# Resistor_Phantom.net
KiCad netlist of a schematic drawn in EAGLE
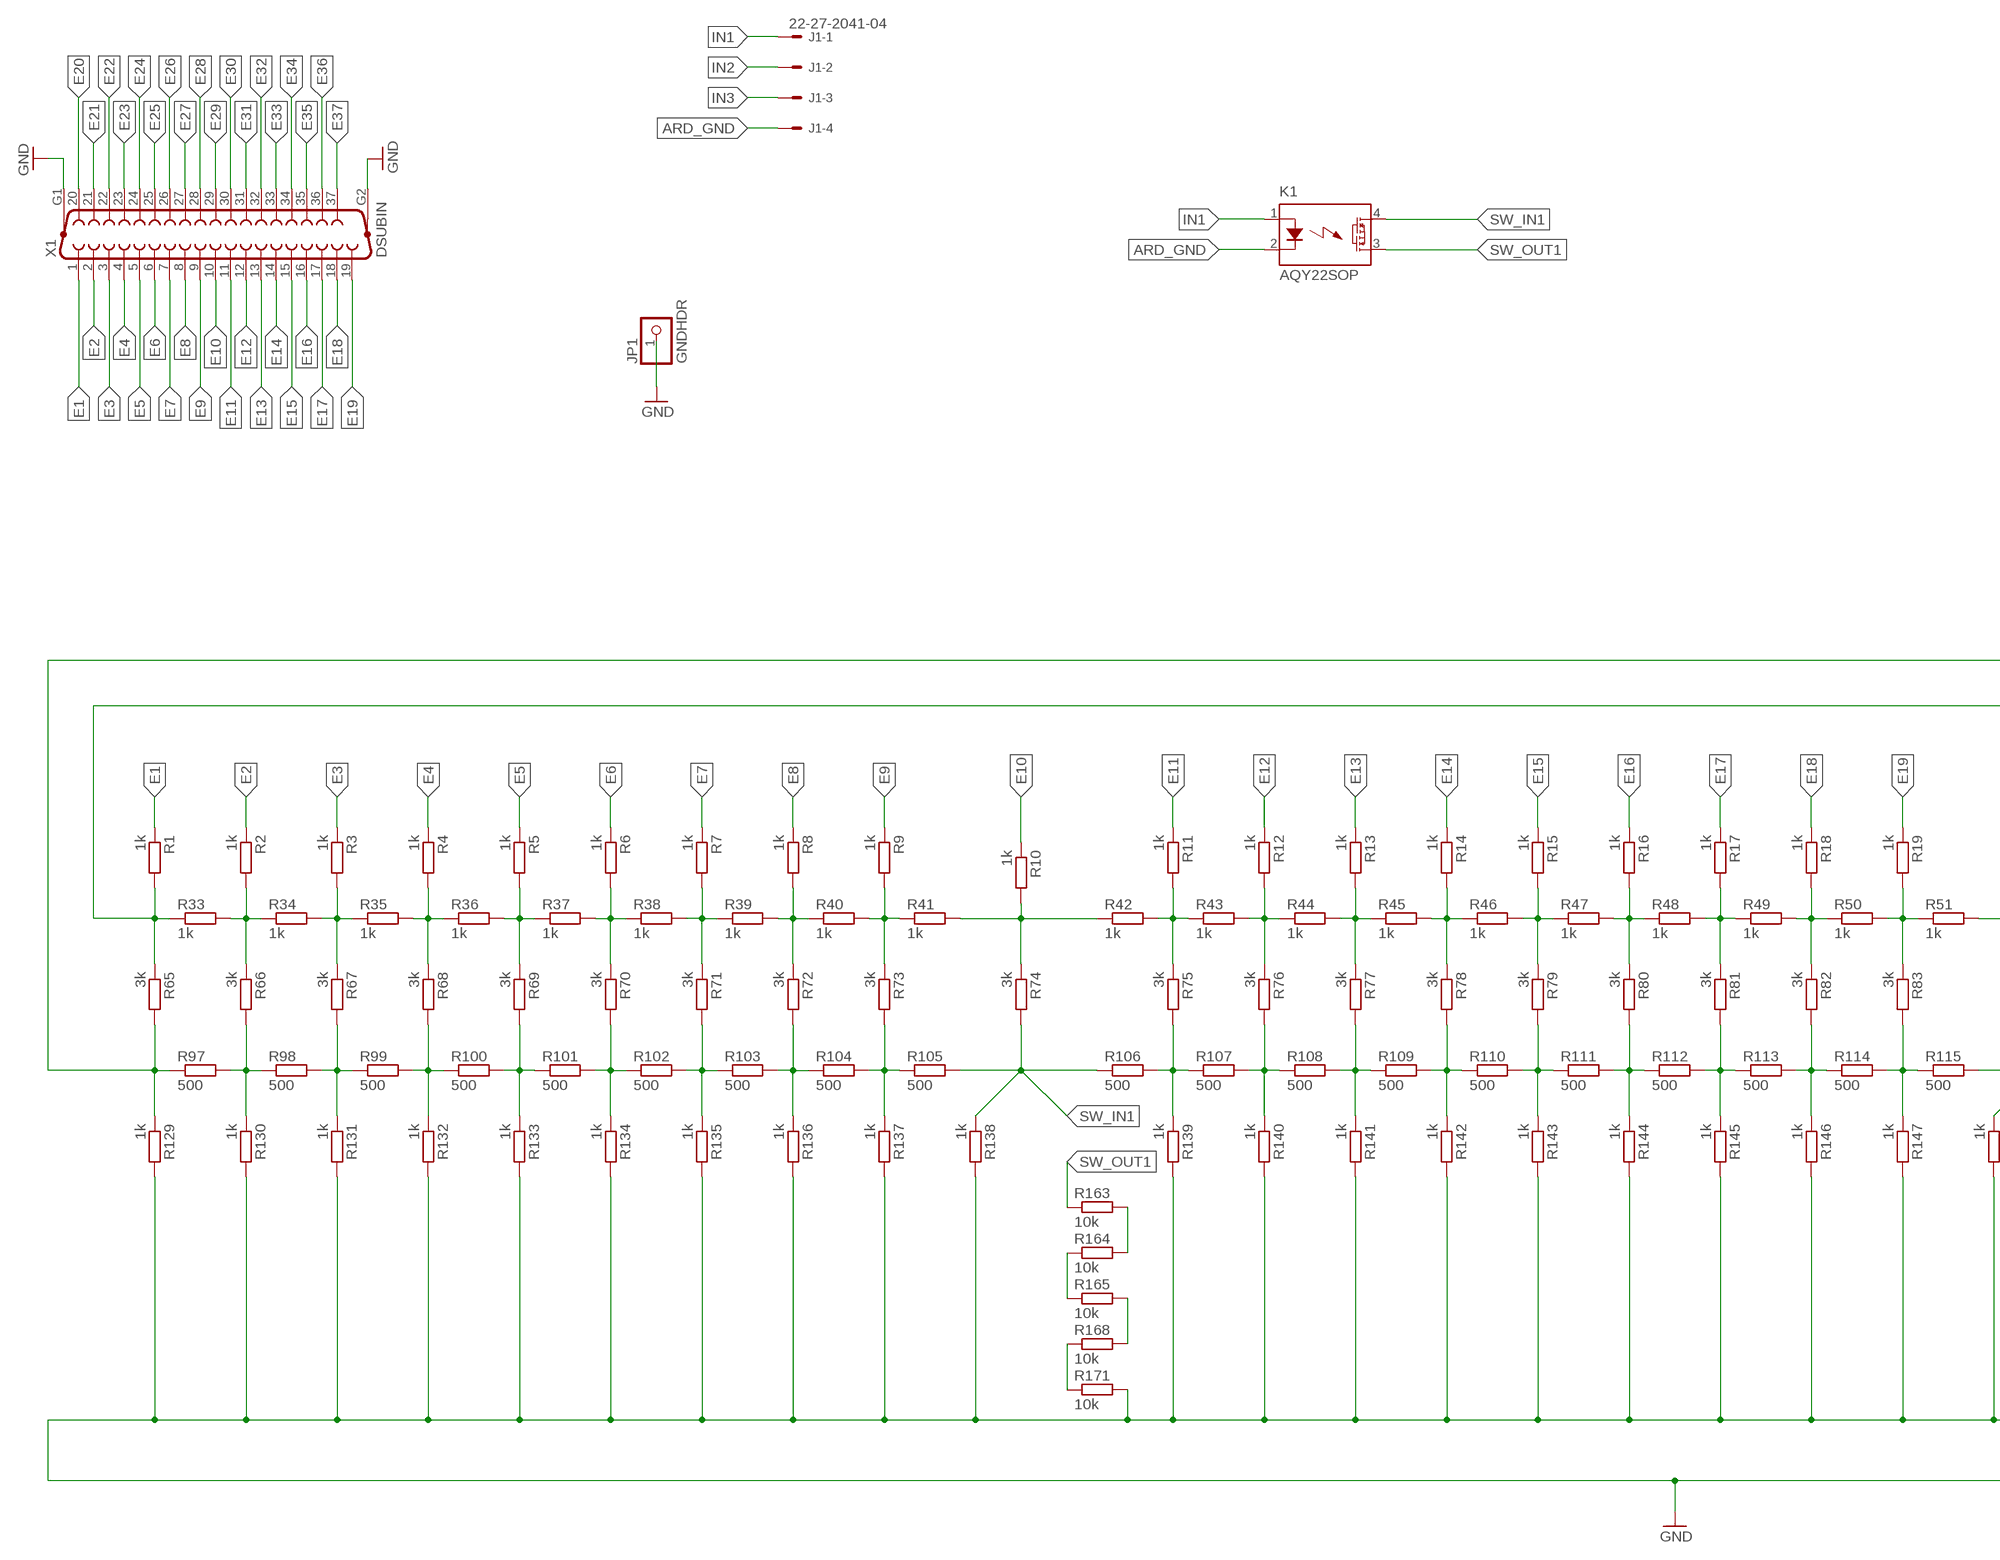
[diagram p0: schematic, sheet 1, part 1 of 2]
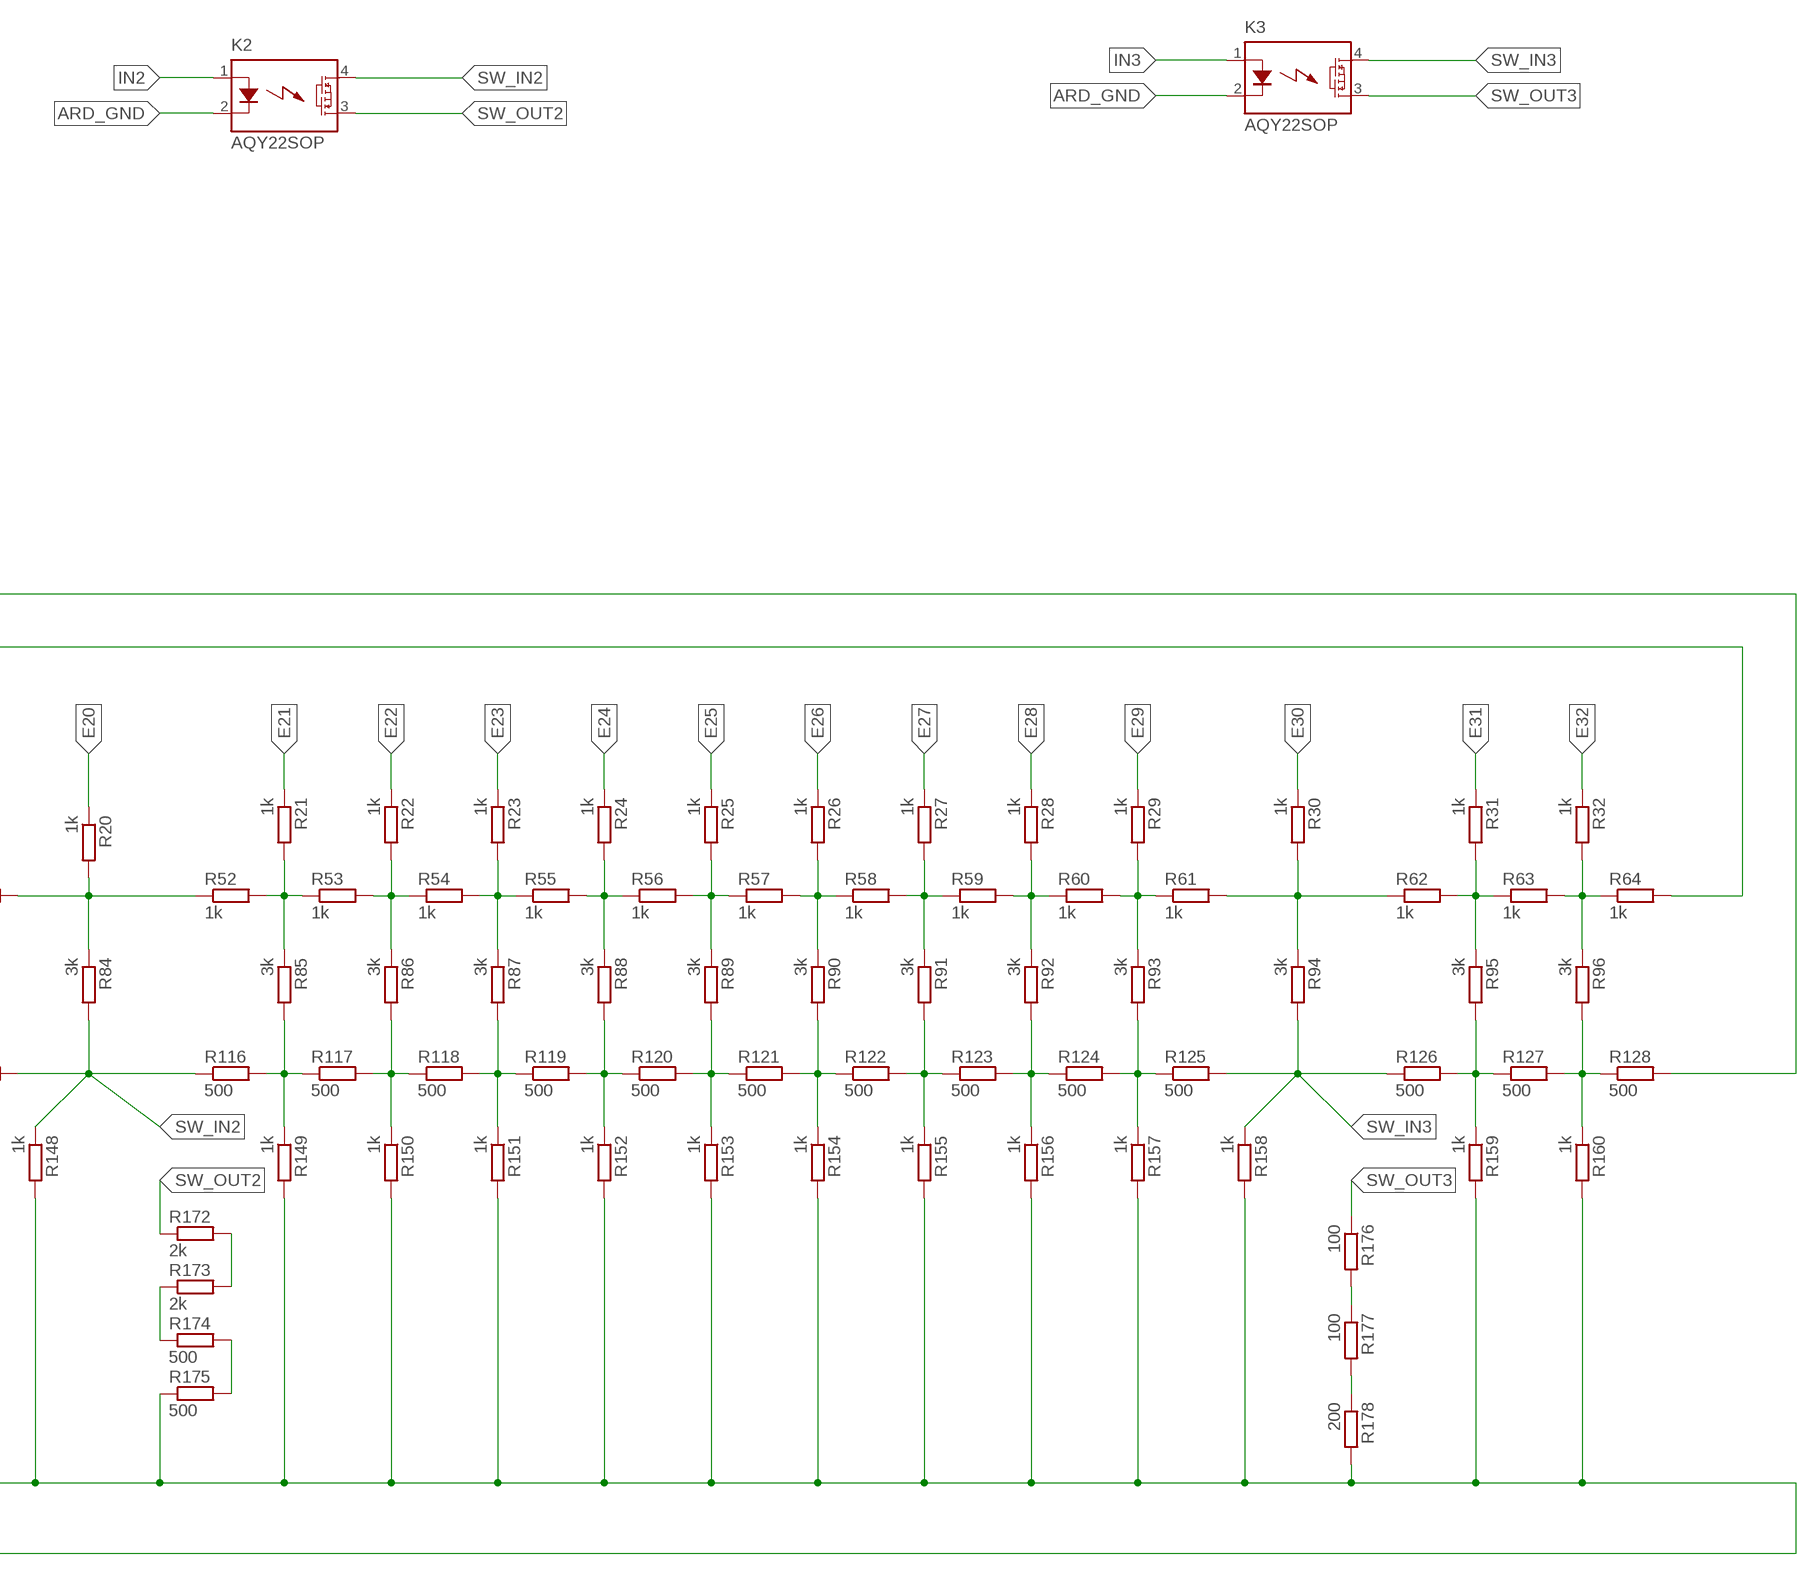
[diagram p1: schematic, sheet 1, part 2 of 2]

(export (version "E")
  (design (tool "Eeschema 10.0.6"))
  (components
    (comp (ref "J1")
      (value "22-27-2041-04")
      (footprint "eagle-import:6410-04")
      (libsource (lib "eagle-import") (part "22-?-0427-2041"))
    )
    (comp (ref "JP1")
      (value "GNDHDR")
      (footprint "eagle-import:1X01")
      (libsource (lib "eagle-import") (part "PINHD-1X1"))
    )
    (comp (ref "K1")
      (value "AQY22SOP")
      (footprint "eagle-import:SOP04")
      (libsource (lib "eagle-import") (part "AQYSOP22"))
    )
    (comp (ref "K2")
      (value "AQY22SOP")
      (footprint "eagle-import:SOP04")
      (libsource (lib "eagle-import") (part "AQYSOP22"))
    )
    (comp (ref "K3")
      (value "AQY22SOP")
      (footprint "eagle-import:SOP04")
      (libsource (lib "eagle-import") (part "AQYSOP22"))
    )
    (comp (ref "R1")
      (value "1k")
      (footprint "eagle-import:R0402")
      (libsource (lib "eagle-import") (part "R-EU_R0402"))
    )
    (comp (ref "R2")
      (value "1k")
      (footprint "eagle-import:R0402")
      (libsource (lib "eagle-import") (part "R-EU_R0402"))
    )
    (comp (ref "R3")
      (value "1k")
      (footprint "eagle-import:R0402")
      (libsource (lib "eagle-import") (part "R-EU_R0402"))
    )
    (comp (ref "R4")
      (value "1k")
      (footprint "eagle-import:R0402")
      (libsource (lib "eagle-import") (part "R-EU_R0402"))
    )
    (comp (ref "R5")
      (value "1k")
      (footprint "eagle-import:R0402")
      (libsource (lib "eagle-import") (part "R-EU_R0402"))
    )
    (comp (ref "R6")
      (value "1k")
      (footprint "eagle-import:R0402")
      (libsource (lib "eagle-import") (part "R-EU_R0402"))
    )
    (comp (ref "R7")
      (value "1k")
      (footprint "eagle-import:R0402")
      (libsource (lib "eagle-import") (part "R-EU_R0402"))
    )
    (comp (ref "R8")
      (value "1k")
      (footprint "eagle-import:R0402")
      (libsource (lib "eagle-import") (part "R-EU_R0402"))
    )
    (comp (ref "R9")
      (value "1k")
      (footprint "eagle-import:R0402")
      (libsource (lib "eagle-import") (part "R-EU_R0402"))
    )
    (comp (ref "R10")
      (value "1k")
      (footprint "eagle-import:R0402")
      (libsource (lib "eagle-import") (part "R-EU_R0402"))
    )
    (comp (ref "R11")
      (value "1k")
      (footprint "eagle-import:R0402")
      (libsource (lib "eagle-import") (part "R-EU_R0402"))
    )
    (comp (ref "R12")
      (value "1k")
      (footprint "eagle-import:R0402")
      (libsource (lib "eagle-import") (part "R-EU_R0402"))
    )
    (comp (ref "R13")
      (value "1k")
      (footprint "eagle-import:R0402")
      (libsource (lib "eagle-import") (part "R-EU_R0402"))
    )
    (comp (ref "R14")
      (value "1k")
      (footprint "eagle-import:R0402")
      (libsource (lib "eagle-import") (part "R-EU_R0402"))
    )
    (comp (ref "R15")
      (value "1k")
      (footprint "eagle-import:R0402")
      (libsource (lib "eagle-import") (part "R-EU_R0402"))
    )
    (comp (ref "R16")
      (value "1k")
      (footprint "eagle-import:R0402")
      (libsource (lib "eagle-import") (part "R-EU_R0402"))
    )
    (comp (ref "R17")
      (value "1k")
      (footprint "eagle-import:R0402")
      (libsource (lib "eagle-import") (part "R-EU_R0402"))
    )
    (comp (ref "R18")
      (value "1k")
      (footprint "eagle-import:R0402")
      (libsource (lib "eagle-import") (part "R-EU_R0402"))
    )
    (comp (ref "R19")
      (value "1k")
      (footprint "eagle-import:R0402")
      (libsource (lib "eagle-import") (part "R-EU_R0402"))
    )
    (comp (ref "R20")
      (value "1k")
      (footprint "eagle-import:R0402")
      (libsource (lib "eagle-import") (part "R-EU_R0402"))
    )
    (comp (ref "R21")
      (value "1k")
      (footprint "eagle-import:R0402")
      (libsource (lib "eagle-import") (part "R-EU_R0402"))
    )
    (comp (ref "R22")
      (value "1k")
      (footprint "eagle-import:R0402")
      (libsource (lib "eagle-import") (part "R-EU_R0402"))
    )
    (comp (ref "R23")
      (value "1k")
      (footprint "eagle-import:R0402")
      (libsource (lib "eagle-import") (part "R-EU_R0402"))
    )
    (comp (ref "R24")
      (value "1k")
      (footprint "eagle-import:R0402")
      (libsource (lib "eagle-import") (part "R-EU_R0402"))
    )
    (comp (ref "R25")
      (value "1k")
      (footprint "eagle-import:R0402")
      (libsource (lib "eagle-import") (part "R-EU_R0402"))
    )
    (comp (ref "R26")
      (value "1k")
      (footprint "eagle-import:R0402")
      (libsource (lib "eagle-import") (part "R-EU_R0402"))
    )
    (comp (ref "R27")
      (value "1k")
      (footprint "eagle-import:R0402")
      (libsource (lib "eagle-import") (part "R-EU_R0402"))
    )
    (comp (ref "R28")
      (value "1k")
      (footprint "eagle-import:R0402")
      (libsource (lib "eagle-import") (part "R-EU_R0402"))
    )
    (comp (ref "R29")
      (value "1k")
      (footprint "eagle-import:R0402")
      (libsource (lib "eagle-import") (part "R-EU_R0402"))
    )
    (comp (ref "R30")
      (value "1k")
      (footprint "eagle-import:R0402")
      (libsource (lib "eagle-import") (part "R-EU_R0402"))
    )
    (comp (ref "R31")
      (value "1k")
      (footprint "eagle-import:R0402")
      (libsource (lib "eagle-import") (part "R-EU_R0402"))
    )
    (comp (ref "R32")
      (value "1k")
      (footprint "eagle-import:R0402")
      (libsource (lib "eagle-import") (part "R-EU_R0402"))
    )
    (comp (ref "R33")
      (value "1k")
      (footprint "eagle-import:R0402")
      (libsource (lib "eagle-import") (part "R-EU_R0402"))
    )
    (comp (ref "R34")
      (value "1k")
      (footprint "eagle-import:R0402")
      (libsource (lib "eagle-import") (part "R-EU_R0402"))
    )
    (comp (ref "R35")
      (value "1k")
      (footprint "eagle-import:R0402")
      (libsource (lib "eagle-import") (part "R-EU_R0402"))
    )
    (comp (ref "R36")
      (value "1k")
      (footprint "eagle-import:R0402")
      (libsource (lib "eagle-import") (part "R-EU_R0402"))
    )
    (comp (ref "R37")
      (value "1k")
      (footprint "eagle-import:R0402")
      (libsource (lib "eagle-import") (part "R-EU_R0402"))
    )
    (comp (ref "R38")
      (value "1k")
      (footprint "eagle-import:R0402")
      (libsource (lib "eagle-import") (part "R-EU_R0402"))
    )
    (comp (ref "R39")
      (value "1k")
      (footprint "eagle-import:R0402")
      (libsource (lib "eagle-import") (part "R-EU_R0402"))
    )
    (comp (ref "R40")
      (value "1k")
      (footprint "eagle-import:R0402")
      (libsource (lib "eagle-import") (part "R-EU_R0402"))
    )
    (comp (ref "R41")
      (value "1k")
      (footprint "eagle-import:R0402")
      (libsource (lib "eagle-import") (part "R-EU_R0402"))
    )
    (comp (ref "R42")
      (value "1k")
      (footprint "eagle-import:R0402")
      (libsource (lib "eagle-import") (part "R-EU_R0402"))
    )
    (comp (ref "R43")
      (value "1k")
      (footprint "eagle-import:R0402")
      (libsource (lib "eagle-import") (part "R-EU_R0402"))
    )
    (comp (ref "R44")
      (value "1k")
      (footprint "eagle-import:R0402")
      (libsource (lib "eagle-import") (part "R-EU_R0402"))
    )
    (comp (ref "R45")
      (value "1k")
      (footprint "eagle-import:R0402")
      (libsource (lib "eagle-import") (part "R-EU_R0402"))
    )
    (comp (ref "R46")
      (value "1k")
      (footprint "eagle-import:R0402")
      (libsource (lib "eagle-import") (part "R-EU_R0402"))
    )
    (comp (ref "R47")
      (value "1k")
      (footprint "eagle-import:R0402")
      (libsource (lib "eagle-import") (part "R-EU_R0402"))
    )
    (comp (ref "R48")
      (value "1k")
      (footprint "eagle-import:R0402")
      (libsource (lib "eagle-import") (part "R-EU_R0402"))
    )
    (comp (ref "R49")
      (value "1k")
      (footprint "eagle-import:R0402")
      (libsource (lib "eagle-import") (part "R-EU_R0402"))
    )
    (comp (ref "R50")
      (value "1k")
      (footprint "eagle-import:R0402")
      (libsource (lib "eagle-import") (part "R-EU_R0402"))
    )
    (comp (ref "R51")
      (value "1k")
      (footprint "eagle-import:R0402")
      (libsource (lib "eagle-import") (part "R-EU_R0402"))
    )
    (comp (ref "R52")
      (value "1k")
      (footprint "eagle-import:R0402")
      (libsource (lib "eagle-import") (part "R-EU_R0402"))
    )
    (comp (ref "R53")
      (value "1k")
      (footprint "eagle-import:R0402")
      (libsource (lib "eagle-import") (part "R-EU_R0402"))
    )
    (comp (ref "R54")
      (value "1k")
      (footprint "eagle-import:R0402")
      (libsource (lib "eagle-import") (part "R-EU_R0402"))
    )
    (comp (ref "R55")
      (value "1k")
      (footprint "eagle-import:R0402")
      (libsource (lib "eagle-import") (part "R-EU_R0402"))
    )
    (comp (ref "R56")
      (value "1k")
      (footprint "eagle-import:R0402")
      (libsource (lib "eagle-import") (part "R-EU_R0402"))
    )
    (comp (ref "R57")
      (value "1k")
      (footprint "eagle-import:R0402")
      (libsource (lib "eagle-import") (part "R-EU_R0402"))
    )
    (comp (ref "R58")
      (value "1k")
      (footprint "eagle-import:R0402")
      (libsource (lib "eagle-import") (part "R-EU_R0402"))
    )
    (comp (ref "R59")
      (value "1k")
      (footprint "eagle-import:R0402")
      (libsource (lib "eagle-import") (part "R-EU_R0402"))
    )
    (comp (ref "R60")
      (value "1k")
      (footprint "eagle-import:R0402")
      (libsource (lib "eagle-import") (part "R-EU_R0402"))
    )
    (comp (ref "R61")
      (value "1k")
      (footprint "eagle-import:R0402")
      (libsource (lib "eagle-import") (part "R-EU_R0402"))
    )
    (comp (ref "R62")
      (value "1k")
      (footprint "eagle-import:R0402")
      (libsource (lib "eagle-import") (part "R-EU_R0402"))
    )
    (comp (ref "R63")
      (value "1k")
      (footprint "eagle-import:R0402")
      (libsource (lib "eagle-import") (part "R-EU_R0402"))
    )
    (comp (ref "R64")
      (value "1k")
      (footprint "eagle-import:R0402")
      (libsource (lib "eagle-import") (part "R-EU_R0402"))
    )
    (comp (ref "R65")
      (value "3k")
      (footprint "eagle-import:R0402")
      (libsource (lib "eagle-import") (part "R-EU_R0402"))
    )
    (comp (ref "R66")
      (value "3k")
      (footprint "eagle-import:R0402")
      (libsource (lib "eagle-import") (part "R-EU_R0402"))
    )
    (comp (ref "R67")
      (value "3k")
      (footprint "eagle-import:R0402")
      (libsource (lib "eagle-import") (part "R-EU_R0402"))
    )
    (comp (ref "R68")
      (value "3k")
      (footprint "eagle-import:R0402")
      (libsource (lib "eagle-import") (part "R-EU_R0402"))
    )
    (comp (ref "R69")
      (value "3k")
      (footprint "eagle-import:R0402")
      (libsource (lib "eagle-import") (part "R-EU_R0402"))
    )
    (comp (ref "R70")
      (value "3k")
      (footprint "eagle-import:R0402")
      (libsource (lib "eagle-import") (part "R-EU_R0402"))
    )
    (comp (ref "R71")
      (value "3k")
      (footprint "eagle-import:R0402")
      (libsource (lib "eagle-import") (part "R-EU_R0402"))
    )
    (comp (ref "R72")
      (value "3k")
      (footprint "eagle-import:R0402")
      (libsource (lib "eagle-import") (part "R-EU_R0402"))
    )
    (comp (ref "R73")
      (value "3k")
      (footprint "eagle-import:R0402")
      (libsource (lib "eagle-import") (part "R-EU_R0402"))
    )
    (comp (ref "R74")
      (value "3k")
      (footprint "eagle-import:R0402")
      (libsource (lib "eagle-import") (part "R-EU_R0402"))
    )
    (comp (ref "R75")
      (value "3k")
      (footprint "eagle-import:R0402")
      (libsource (lib "eagle-import") (part "R-EU_R0402"))
    )
    (comp (ref "R76")
      (value "3k")
      (footprint "eagle-import:R0402")
      (libsource (lib "eagle-import") (part "R-EU_R0402"))
    )
    (comp (ref "R77")
      (value "3k")
      (footprint "eagle-import:R0402")
      (libsource (lib "eagle-import") (part "R-EU_R0402"))
    )
    (comp (ref "R78")
      (value "3k")
      (footprint "eagle-import:R0402")
      (libsource (lib "eagle-import") (part "R-EU_R0402"))
    )
    (comp (ref "R79")
      (value "3k")
      (footprint "eagle-import:R0402")
      (libsource (lib "eagle-import") (part "R-EU_R0402"))
    )
    (comp (ref "R80")
      (value "3k")
      (footprint "eagle-import:R0402")
      (libsource (lib "eagle-import") (part "R-EU_R0402"))
    )
    (comp (ref "R81")
      (value "3k")
      (footprint "eagle-import:R0402")
      (libsource (lib "eagle-import") (part "R-EU_R0402"))
    )
    (comp (ref "R82")
      (value "3k")
      (footprint "eagle-import:R0402")
      (libsource (lib "eagle-import") (part "R-EU_R0402"))
    )
    (comp (ref "R83")
      (value "3k")
      (footprint "eagle-import:R0402")
      (libsource (lib "eagle-import") (part "R-EU_R0402"))
    )
    (comp (ref "R84")
      (value "3k")
      (footprint "eagle-import:R0402")
      (libsource (lib "eagle-import") (part "R-EU_R0402"))
    )
    (comp (ref "R85")
      (value "3k")
      (footprint "eagle-import:R0402")
      (libsource (lib "eagle-import") (part "R-EU_R0402"))
    )
    (comp (ref "R86")
      (value "3k")
      (footprint "eagle-import:R0402")
      (libsource (lib "eagle-import") (part "R-EU_R0402"))
    )
    (comp (ref "R87")
      (value "3k")
      (footprint "eagle-import:R0402")
      (libsource (lib "eagle-import") (part "R-EU_R0402"))
    )
    (comp (ref "R88")
      (value "3k")
      (footprint "eagle-import:R0402")
      (libsource (lib "eagle-import") (part "R-EU_R0402"))
    )
    (comp (ref "R89")
      (value "3k")
      (footprint "eagle-import:R0402")
      (libsource (lib "eagle-import") (part "R-EU_R0402"))
    )
    (comp (ref "R90")
      (value "3k")
      (footprint "eagle-import:R0402")
      (libsource (lib "eagle-import") (part "R-EU_R0402"))
    )
    (comp (ref "R91")
      (value "3k")
      (footprint "eagle-import:R0402")
      (libsource (lib "eagle-import") (part "R-EU_R0402"))
    )
    (comp (ref "R92")
      (value "3k")
      (footprint "eagle-import:R0402")
      (libsource (lib "eagle-import") (part "R-EU_R0402"))
    )
    (comp (ref "R93")
      (value "3k")
      (footprint "eagle-import:R0402")
      (libsource (lib "eagle-import") (part "R-EU_R0402"))
    )
    (comp (ref "R94")
      (value "3k")
      (footprint "eagle-import:R0402")
      (libsource (lib "eagle-import") (part "R-EU_R0402"))
    )
    (comp (ref "R95")
      (value "3k")
      (footprint "eagle-import:R0402")
      (libsource (lib "eagle-import") (part "R-EU_R0402"))
    )
    (comp (ref "R96")
      (value "3k")
      (footprint "eagle-import:R0402")
      (libsource (lib "eagle-import") (part "R-EU_R0402"))
    )
    (comp (ref "R97")
      (value "500")
      (footprint "eagle-import:R0402")
      (libsource (lib "eagle-import") (part "R-EU_R0402"))
    )
    (comp (ref "R98")
      (value "500")
      (footprint "eagle-import:R0402")
      (libsource (lib "eagle-import") (part "R-EU_R0402"))
    )
    (comp (ref "R99")
      (value "500")
      (footprint "eagle-import:R0402")
      (libsource (lib "eagle-import") (part "R-EU_R0402"))
    )
    (comp (ref "R100")
      (value "500")
      (footprint "eagle-import:R0402")
      (libsource (lib "eagle-import") (part "R-EU_R0402"))
    )
    (comp (ref "R101")
      (value "500")
      (footprint "eagle-import:R0402")
      (libsource (lib "eagle-import") (part "R-EU_R0402"))
    )
    (comp (ref "R102")
      (value "500")
      (footprint "eagle-import:R0402")
      (libsource (lib "eagle-import") (part "R-EU_R0402"))
    )
    (comp (ref "R103")
      (value "500")
      (footprint "eagle-import:R0402")
      (libsource (lib "eagle-import") (part "R-EU_R0402"))
    )
    (comp (ref "R104")
      (value "500")
      (footprint "eagle-import:R0402")
      (libsource (lib "eagle-import") (part "R-EU_R0402"))
    )
    (comp (ref "R105")
      (value "500")
      (footprint "eagle-import:R0402")
      (libsource (lib "eagle-import") (part "R-EU_R0402"))
    )
    (comp (ref "R106")
      (value "500")
      (footprint "eagle-import:R0402")
      (libsource (lib "eagle-import") (part "R-EU_R0402"))
    )
    (comp (ref "R107")
      (value "500")
      (footprint "eagle-import:R0402")
      (libsource (lib "eagle-import") (part "R-EU_R0402"))
    )
    (comp (ref "R108")
      (value "500")
      (footprint "eagle-import:R0402")
      (libsource (lib "eagle-import") (part "R-EU_R0402"))
    )
    (comp (ref "R109")
      (value "500")
      (footprint "eagle-import:R0402")
      (libsource (lib "eagle-import") (part "R-EU_R0402"))
    )
    (comp (ref "R110")
      (value "500")
      (footprint "eagle-import:R0402")
      (libsource (lib "eagle-import") (part "R-EU_R0402"))
    )
    (comp (ref "R111")
      (value "500")
      (footprint "eagle-import:R0402")
      (libsource (lib "eagle-import") (part "R-EU_R0402"))
    )
    (comp (ref "R112")
      (value "500")
      (footprint "eagle-import:R0402")
      (libsource (lib "eagle-import") (part "R-EU_R0402"))
    )
    (comp (ref "R113")
      (value "500")
      (footprint "eagle-import:R0402")
      (libsource (lib "eagle-import") (part "R-EU_R0402"))
    )
    (comp (ref "R114")
      (value "500")
      (footprint "eagle-import:R0402")
      (libsource (lib "eagle-import") (part "R-EU_R0402"))
    )
    (comp (ref "R115")
      (value "500")
      (footprint "eagle-import:R0402")
      (libsource (lib "eagle-import") (part "R-EU_R0402"))
    )
    (comp (ref "R116")
      (value "500")
      (footprint "eagle-import:R0402")
      (libsource (lib "eagle-import") (part "R-EU_R0402"))
    )
    (comp (ref "R117")
      (value "500")
      (footprint "eagle-import:R0402")
      (libsource (lib "eagle-import") (part "R-EU_R0402"))
    )
    (comp (ref "R118")
      (value "500")
      (footprint "eagle-import:R0402")
      (libsource (lib "eagle-import") (part "R-EU_R0402"))
    )
    (comp (ref "R119")
      (value "500")
      (footprint "eagle-import:R0402")
      (libsource (lib "eagle-import") (part "R-EU_R0402"))
    )
    (comp (ref "R120")
      (value "500")
      (footprint "eagle-import:R0402")
      (libsource (lib "eagle-import") (part "R-EU_R0402"))
    )
    (comp (ref "R121")
      (value "500")
      (footprint "eagle-import:R0402")
      (libsource (lib "eagle-import") (part "R-EU_R0402"))
    )
    (comp (ref "R122")
      (value "500")
      (footprint "eagle-import:R0402")
      (libsource (lib "eagle-import") (part "R-EU_R0402"))
    )
    (comp (ref "R123")
      (value "500")
      (footprint "eagle-import:R0402")
      (libsource (lib "eagle-import") (part "R-EU_R0402"))
    )
    (comp (ref "R124")
      (value "500")
      (footprint "eagle-import:R0402")
      (libsource (lib "eagle-import") (part "R-EU_R0402"))
    )
    (comp (ref "R125")
      (value "500")
      (footprint "eagle-import:R0402")
      (libsource (lib "eagle-import") (part "R-EU_R0402"))
    )
    (comp (ref "R126")
      (value "500")
      (footprint "eagle-import:R0402")
      (libsource (lib "eagle-import") (part "R-EU_R0402"))
    )
    (comp (ref "R127")
      (value "500")
      (footprint "eagle-import:R0402")
      (libsource (lib "eagle-import") (part "R-EU_R0402"))
    )
    (comp (ref "R128")
      (value "500")
      (footprint "eagle-import:R0402")
      (libsource (lib "eagle-import") (part "R-EU_R0402"))
    )
    (comp (ref "R129")
      (value "1k")
      (footprint "eagle-import:R0402")
      (libsource (lib "eagle-import") (part "R-EU_R0402"))
    )
    (comp (ref "R130")
      (value "1k")
      (footprint "eagle-import:R0402")
      (libsource (lib "eagle-import") (part "R-EU_R0402"))
    )
    (comp (ref "R131")
      (value "1k")
      (footprint "eagle-import:R0402")
      (libsource (lib "eagle-import") (part "R-EU_R0402"))
    )
    (comp (ref "R132")
      (value "1k")
      (footprint "eagle-import:R0402")
      (libsource (lib "eagle-import") (part "R-EU_R0402"))
    )
    (comp (ref "R133")
      (value "1k")
      (footprint "eagle-import:R0402")
      (libsource (lib "eagle-import") (part "R-EU_R0402"))
    )
    (comp (ref "R134")
      (value "1k")
      (footprint "eagle-import:R0402")
      (libsource (lib "eagle-import") (part "R-EU_R0402"))
    )
    (comp (ref "R135")
      (value "1k")
      (footprint "eagle-import:R0402")
      (libsource (lib "eagle-import") (part "R-EU_R0402"))
    )
    (comp (ref "R136")
      (value "1k")
      (footprint "eagle-import:R0402")
      (libsource (lib "eagle-import") (part "R-EU_R0402"))
    )
    (comp (ref "R137")
      (value "1k")
      (footprint "eagle-import:R0402")
      (libsource (lib "eagle-import") (part "R-EU_R0402"))
    )
    (comp (ref "R138")
      (value "1k")
      (footprint "eagle-import:R0402")
      (libsource (lib "eagle-import") (part "R-EU_R0402"))
    )
    (comp (ref "R139")
      (value "1k")
      (footprint "eagle-import:R0402")
      (libsource (lib "eagle-import") (part "R-EU_R0402"))
    )
    (comp (ref "R140")
      (value "1k")
      (footprint "eagle-import:R0402")
      (libsource (lib "eagle-import") (part "R-EU_R0402"))
    )
    (comp (ref "R141")
      (value "1k")
      (footprint "eagle-import:R0402")
      (libsource (lib "eagle-import") (part "R-EU_R0402"))
    )
    (comp (ref "R142")
      (value "1k")
      (footprint "eagle-import:R0402")
      (libsource (lib "eagle-import") (part "R-EU_R0402"))
    )
    (comp (ref "R143")
      (value "1k")
      (footprint "eagle-import:R0402")
      (libsource (lib "eagle-import") (part "R-EU_R0402"))
    )
    (comp (ref "R144")
      (value "1k")
      (footprint "eagle-import:R0402")
      (libsource (lib "eagle-import") (part "R-EU_R0402"))
    )
    (comp (ref "R145")
      (value "1k")
      (footprint "eagle-import:R0402")
      (libsource (lib "eagle-import") (part "R-EU_R0402"))
    )
    (comp (ref "R146")
      (value "1k")
      (footprint "eagle-import:R0402")
      (libsource (lib "eagle-import") (part "R-EU_R0402"))
    )
    (comp (ref "R147")
      (value "1k")
      (footprint "eagle-import:R0402")
      (libsource (lib "eagle-import") (part "R-EU_R0402"))
    )
    (comp (ref "R148")
      (value "1k")
      (footprint "eagle-import:R0402")
      (libsource (lib "eagle-import") (part "R-EU_R0402"))
    )
    (comp (ref "R149")
      (value "1k")
      (footprint "eagle-import:R0402")
      (libsource (lib "eagle-import") (part "R-EU_R0402"))
    )
    (comp (ref "R150")
      (value "1k")
      (footprint "eagle-import:R0402")
      (libsource (lib "eagle-import") (part "R-EU_R0402"))
    )
    (comp (ref "R151")
      (value "1k")
      (footprint "eagle-import:R0402")
      (libsource (lib "eagle-import") (part "R-EU_R0402"))
    )
    (comp (ref "R152")
      (value "1k")
      (footprint "eagle-import:R0402")
      (libsource (lib "eagle-import") (part "R-EU_R0402"))
    )
    (comp (ref "R153")
      (value "1k")
      (footprint "eagle-import:R0402")
      (libsource (lib "eagle-import") (part "R-EU_R0402"))
    )
    (comp (ref "R154")
      (value "1k")
      (footprint "eagle-import:R0402")
      (libsource (lib "eagle-import") (part "R-EU_R0402"))
    )
    (comp (ref "R155")
      (value "1k")
      (footprint "eagle-import:R0402")
      (libsource (lib "eagle-import") (part "R-EU_R0402"))
    )
    (comp (ref "R156")
      (value "1k")
      (footprint "eagle-import:R0402")
      (libsource (lib "eagle-import") (part "R-EU_R0402"))
    )
    (comp (ref "R157")
      (value "1k")
      (footprint "eagle-import:R0402")
      (libsource (lib "eagle-import") (part "R-EU_R0402"))
    )
    (comp (ref "R158")
      (value "1k")
      (footprint "eagle-import:R0402")
      (libsource (lib "eagle-import") (part "R-EU_R0402"))
    )
    (comp (ref "R159")
      (value "1k")
      (footprint "eagle-import:R0402")
      (libsource (lib "eagle-import") (part "R-EU_R0402"))
    )
    (comp (ref "R160")
      (value "1k")
      (footprint "eagle-import:R0402")
      (libsource (lib "eagle-import") (part "R-EU_R0402"))
    )
    (comp (ref "R163")
      (value "10k")
      (footprint "eagle-import:R0402")
      (libsource (lib "eagle-import") (part "R-EU_R0402"))
    )
    (comp (ref "R164")
      (value "10k")
      (footprint "eagle-import:R0402")
      (libsource (lib "eagle-import") (part "R-EU_R0402"))
    )
    (comp (ref "R165")
      (value "10k")
      (footprint "eagle-import:R0402")
      (libsource (lib "eagle-import") (part "R-EU_R0402"))
    )
    (comp (ref "R168")
      (value "10k")
      (footprint "eagle-import:R0402")
      (libsource (lib "eagle-import") (part "R-EU_R0402"))
    )
    (comp (ref "R171")
      (value "10k")
      (footprint "eagle-import:R0402")
      (libsource (lib "eagle-import") (part "R-EU_R0402"))
    )
    (comp (ref "R172")
      (value "2k")
      (footprint "eagle-import:R0402")
      (libsource (lib "eagle-import") (part "R-EU_R0402"))
    )
    (comp (ref "R173")
      (value "2k")
      (footprint "eagle-import:R0402")
      (libsource (lib "eagle-import") (part "R-EU_R0402"))
    )
    (comp (ref "R174")
      (value "500")
      (footprint "eagle-import:R0402")
      (libsource (lib "eagle-import") (part "R-EU_R0402"))
    )
    (comp (ref "R175")
      (value "500")
      (footprint "eagle-import:R0402")
      (libsource (lib "eagle-import") (part "R-EU_R0402"))
    )
    (comp (ref "R176")
      (value "100")
      (footprint "eagle-import:R0402")
      (libsource (lib "eagle-import") (part "R-EU_R0402"))
    )
    (comp (ref "R177")
      (value "100")
      (footprint "eagle-import:R0402")
      (libsource (lib "eagle-import") (part "R-EU_R0402"))
    )
    (comp (ref "R178")
      (value "200")
      (footprint "eagle-import:R0402")
      (libsource (lib "eagle-import") (part "R-EU_R0402"))
    )
    (comp (ref "X1")
      (value "DSUBIN")
      (footprint "eagle-import:F37VP")
      (libsource (lib "eagle-import") (part "F37VP"))
    )
  )
  (nets
    (net (code "1") (name "ARD_GND") (class "Default")
      (node (ref "J1") (pin "4") (pinfunction "S_4") (pintype "passive"))
      (node (ref "K1") (pin "2") (pinfunction "K_2") (pintype "passive"))
      (node (ref "K2") (pin "2") (pinfunction "K_2") (pintype "passive"))
      (node (ref "K3") (pin "2") (pinfunction "K_2") (pintype "passive"))
    )
    (net (code "2") (name "E1") (class "Default")
      (node (ref "R1") (pin "1") (pinfunction "1_1") (pintype "passive"))
      (node (ref "X1") (pin "1") (pinfunction "1_1") (pintype "passive"))
    )
    (net (code "3") (name "E2") (class "Default")
      (node (ref "R2") (pin "1") (pinfunction "1_1") (pintype "passive"))
      (node (ref "X1") (pin "2") (pinfunction "2_2") (pintype "passive"))
    )
    (net (code "4") (name "E3") (class "Default")
      (node (ref "R3") (pin "1") (pinfunction "1_1") (pintype "passive"))
      (node (ref "X1") (pin "3") (pinfunction "3_3") (pintype "passive"))
    )
    (net (code "5") (name "E4") (class "Default")
      (node (ref "R4") (pin "1") (pinfunction "1_1") (pintype "passive"))
      (node (ref "X1") (pin "4") (pinfunction "4_4") (pintype "passive"))
    )
    (net (code "6") (name "E5") (class "Default")
      (node (ref "R5") (pin "1") (pinfunction "1_1") (pintype "passive"))
      (node (ref "X1") (pin "5") (pinfunction "5_5") (pintype "passive"))
    )
    (net (code "7") (name "E6") (class "Default")
      (node (ref "R6") (pin "1") (pinfunction "1_1") (pintype "passive"))
      (node (ref "X1") (pin "6") (pinfunction "6_6") (pintype "passive"))
    )
    (net (code "8") (name "E7") (class "Default")
      (node (ref "R7") (pin "1") (pinfunction "1_1") (pintype "passive"))
      (node (ref "X1") (pin "7") (pinfunction "7_7") (pintype "passive"))
    )
    (net (code "9") (name "E8") (class "Default")
      (node (ref "R8") (pin "1") (pinfunction "1_1") (pintype "passive"))
      (node (ref "X1") (pin "8") (pinfunction "8_8") (pintype "passive"))
    )
    (net (code "10") (name "E9") (class "Default")
      (node (ref "R9") (pin "1") (pinfunction "1_1") (pintype "passive"))
      (node (ref "X1") (pin "9") (pinfunction "9_9") (pintype "passive"))
    )
    (net (code "11") (name "E10") (class "Default")
      (node (ref "R10") (pin "1") (pinfunction "1_1") (pintype "passive"))
      (node (ref "X1") (pin "10") (pinfunction "10_10") (pintype "passive"))
    )
    (net (code "12") (name "E11") (class "Default")
      (node (ref "R11") (pin "1") (pinfunction "1_1") (pintype "passive"))
      (node (ref "X1") (pin "11") (pinfunction "11_11") (pintype "passive"))
    )
    (net (code "13") (name "E12") (class "Default")
      (node (ref "R12") (pin "1") (pinfunction "1_1") (pintype "passive"))
      (node (ref "X1") (pin "12") (pinfunction "12_12") (pintype "passive"))
    )
    (net (code "14") (name "E13") (class "Default")
      (node (ref "R13") (pin "1") (pinfunction "1_1") (pintype "passive"))
      (node (ref "X1") (pin "13") (pinfunction "13_13") (pintype "passive"))
    )
    (net (code "15") (name "E14") (class "Default")
      (node (ref "R14") (pin "1") (pinfunction "1_1") (pintype "passive"))
      (node (ref "X1") (pin "14") (pinfunction "14_14") (pintype "passive"))
    )
    (net (code "16") (name "E15") (class "Default")
      (node (ref "R15") (pin "1") (pinfunction "1_1") (pintype "passive"))
      (node (ref "X1") (pin "15") (pinfunction "15_15") (pintype "passive"))
    )
    (net (code "17") (name "E16") (class "Default")
      (node (ref "R16") (pin "1") (pinfunction "1_1") (pintype "passive"))
      (node (ref "X1") (pin "16") (pinfunction "16_16") (pintype "passive"))
    )
    (net (code "18") (name "E17") (class "Default")
      (node (ref "R17") (pin "1") (pinfunction "1_1") (pintype "passive"))
      (node (ref "X1") (pin "17") (pinfunction "17_17") (pintype "passive"))
    )
    (net (code "19") (name "E18") (class "Default")
      (node (ref "R18") (pin "1") (pinfunction "1_1") (pintype "passive"))
      (node (ref "X1") (pin "18") (pinfunction "18_18") (pintype "passive"))
    )
    (net (code "20") (name "E19") (class "Default")
      (node (ref "R19") (pin "1") (pinfunction "1_1") (pintype "passive"))
      (node (ref "X1") (pin "19") (pinfunction "19_19") (pintype "passive"))
    )
    (net (code "21") (name "E20") (class "Default")
      (node (ref "R20") (pin "1") (pinfunction "1_1") (pintype "passive"))
      (node (ref "X1") (pin "20") (pinfunction "20_20") (pintype "passive"))
    )
    (net (code "22") (name "E21") (class "Default")
      (node (ref "R21") (pin "1") (pinfunction "1_1") (pintype "passive"))
      (node (ref "X1") (pin "21") (pinfunction "21_21") (pintype "passive"))
    )
    (net (code "23") (name "E22") (class "Default")
      (node (ref "R22") (pin "1") (pinfunction "1_1") (pintype "passive"))
      (node (ref "X1") (pin "22") (pinfunction "22_22") (pintype "passive"))
    )
    (net (code "24") (name "E23") (class "Default")
      (node (ref "R23") (pin "1") (pinfunction "1_1") (pintype "passive"))
      (node (ref "X1") (pin "23") (pinfunction "23_23") (pintype "passive"))
    )
    (net (code "25") (name "E24") (class "Default")
      (node (ref "R24") (pin "1") (pinfunction "1_1") (pintype "passive"))
      (node (ref "X1") (pin "24") (pinfunction "24_24") (pintype "passive"))
    )
    (net (code "26") (name "E25") (class "Default")
      (node (ref "R25") (pin "1") (pinfunction "1_1") (pintype "passive"))
      (node (ref "X1") (pin "25") (pinfunction "25_25") (pintype "passive"))
    )
    (net (code "27") (name "E26") (class "Default")
      (node (ref "R26") (pin "1") (pinfunction "1_1") (pintype "passive"))
      (node (ref "X1") (pin "26") (pinfunction "26_26") (pintype "passive"))
    )
    (net (code "28") (name "E27") (class "Default")
      (node (ref "R27") (pin "1") (pinfunction "1_1") (pintype "passive"))
      (node (ref "X1") (pin "27") (pinfunction "27_27") (pintype "passive"))
    )
    (net (code "29") (name "E28") (class "Default")
      (node (ref "R28") (pin "1") (pinfunction "1_1") (pintype "passive"))
      (node (ref "X1") (pin "28") (pinfunction "28_28") (pintype "passive"))
    )
    (net (code "30") (name "E29") (class "Default")
      (node (ref "R29") (pin "1") (pinfunction "1_1") (pintype "passive"))
      (node (ref "X1") (pin "29") (pinfunction "29_29") (pintype "passive"))
    )
    (net (code "31") (name "E30") (class "Default")
      (node (ref "R30") (pin "1") (pinfunction "1_1") (pintype "passive"))
      (node (ref "X1") (pin "30") (pinfunction "30_30") (pintype "passive"))
    )
    (net (code "32") (name "E31") (class "Default")
      (node (ref "R31") (pin "1") (pinfunction "1_1") (pintype "passive"))
      (node (ref "X1") (pin "31") (pinfunction "31_31") (pintype "passive"))
    )
    (net (code "33") (name "E32") (class "Default")
      (node (ref "R32") (pin "1") (pinfunction "1_1") (pintype "passive"))
      (node (ref "X1") (pin "32") (pinfunction "32_32") (pintype "passive"))
    )
    (net (code "34") (name "E33") (class "Default")
      (node (ref "X1") (pin "33") (pinfunction "33_33") (pintype "passive"))
    )
    (net (code "35") (name "E34") (class "Default")
      (node (ref "X1") (pin "34") (pinfunction "34_34") (pintype "passive"))
    )
    (net (code "36") (name "E35") (class "Default")
      (node (ref "X1") (pin "35") (pinfunction "35_35") (pintype "passive"))
    )
    (net (code "37") (name "E36") (class "Default")
      (node (ref "X1") (pin "36") (pinfunction "36_36") (pintype "passive"))
    )
    (net (code "38") (name "E37") (class "Default")
      (node (ref "X1") (pin "37") (pinfunction "37_37") (pintype "passive"))
    )
    (net (code "39") (name "GND") (class "Default")
      (node (ref "JP1") (pin "1") (pinfunction "1_1") (pintype "passive"))
      (node (ref "R129") (pin "2") (pinfunction "2_2") (pintype "passive"))
      (node (ref "R130") (pin "2") (pinfunction "2_2") (pintype "passive"))
      (node (ref "R131") (pin "2") (pinfunction "2_2") (pintype "passive"))
      (node (ref "R132") (pin "2") (pinfunction "2_2") (pintype "passive"))
      (node (ref "R133") (pin "2") (pinfunction "2_2") (pintype "passive"))
      (node (ref "R134") (pin "2") (pinfunction "2_2") (pintype "passive"))
      (node (ref "R135") (pin "2") (pinfunction "2_2") (pintype "passive"))
      (node (ref "R136") (pin "2") (pinfunction "2_2") (pintype "passive"))
      (node (ref "R137") (pin "2") (pinfunction "2_2") (pintype "passive"))
      (node (ref "R138") (pin "2") (pinfunction "2_2") (pintype "passive"))
      (node (ref "R139") (pin "2") (pinfunction "2_2") (pintype "passive"))
      (node (ref "R140") (pin "2") (pinfunction "2_2") (pintype "passive"))
      (node (ref "R141") (pin "2") (pinfunction "2_2") (pintype "passive"))
      (node (ref "R142") (pin "2") (pinfunction "2_2") (pintype "passive"))
      (node (ref "R143") (pin "2") (pinfunction "2_2") (pintype "passive"))
      (node (ref "R144") (pin "2") (pinfunction "2_2") (pintype "passive"))
      (node (ref "R145") (pin "2") (pinfunction "2_2") (pintype "passive"))
      (node (ref "R146") (pin "2") (pinfunction "2_2") (pintype "passive"))
      (node (ref "R147") (pin "2") (pinfunction "2_2") (pintype "passive"))
      (node (ref "R148") (pin "2") (pinfunction "2_2") (pintype "passive"))
      (node (ref "R149") (pin "2") (pinfunction "2_2") (pintype "passive"))
      (node (ref "R150") (pin "2") (pinfunction "2_2") (pintype "passive"))
      (node (ref "R151") (pin "2") (pinfunction "2_2") (pintype "passive"))
      (node (ref "R152") (pin "2") (pinfunction "2_2") (pintype "passive"))
      (node (ref "R153") (pin "2") (pinfunction "2_2") (pintype "passive"))
      (node (ref "R154") (pin "2") (pinfunction "2_2") (pintype "passive"))
      (node (ref "R155") (pin "2") (pinfunction "2_2") (pintype "passive"))
      (node (ref "R156") (pin "2") (pinfunction "2_2") (pintype "passive"))
      (node (ref "R157") (pin "2") (pinfunction "2_2") (pintype "passive"))
      (node (ref "R158") (pin "2") (pinfunction "2_2") (pintype "passive"))
      (node (ref "R159") (pin "2") (pinfunction "2_2") (pintype "passive"))
      (node (ref "R160") (pin "2") (pinfunction "2_2") (pintype "passive"))
      (node (ref "R171") (pin "2") (pinfunction "2_2") (pintype "passive"))
      (node (ref "R175") (pin "1") (pinfunction "1_1") (pintype "passive"))
      (node (ref "R178") (pin "2") (pinfunction "2_2") (pintype "passive"))
      (node (ref "X1") (pin "G1") (pinfunction "G1_G1") (pintype "passive"))
      (node (ref "X1") (pin "G2") (pinfunction "G2_G2") (pintype "passive"))
    )
    (net (code "40") (name "IN1") (class "Default")
      (node (ref "J1") (pin "1") (pinfunction "S_1") (pintype "passive"))
      (node (ref "K1") (pin "1") (pinfunction "A_1") (pintype "passive"))
    )
    (net (code "41") (name "IN2") (class "Default")
      (node (ref "J1") (pin "2") (pinfunction "S_2") (pintype "passive"))
      (node (ref "K2") (pin "1") (pinfunction "A_1") (pintype "passive"))
    )
    (net (code "42") (name "IN3") (class "Default")
      (node (ref "J1") (pin "3") (pinfunction "S_3") (pintype "passive"))
      (node (ref "K3") (pin "1") (pinfunction "A_1") (pintype "passive"))
    )
    (net (code "43") (name "Net-(R1-Pad2)") (class "Default")
      (node (ref "R1") (pin "2") (pinfunction "2_2") (pintype "passive"))
      (node (ref "R33") (pin "1") (pinfunction "1_1") (pintype "passive"))
      (node (ref "R64") (pin "2") (pinfunction "2_2") (pintype "passive"))
      (node (ref "R65") (pin "1") (pinfunction "1_1") (pintype "passive"))
    )
    (net (code "44") (name "Net-(R2-Pad2)") (class "Default")
      (node (ref "R2") (pin "2") (pinfunction "2_2") (pintype "passive"))
      (node (ref "R33") (pin "2") (pinfunction "2_2") (pintype "passive"))
      (node (ref "R34") (pin "1") (pinfunction "1_1") (pintype "passive"))
      (node (ref "R66") (pin "1") (pinfunction "1_1") (pintype "passive"))
    )
    (net (code "45") (name "Net-(R3-Pad2)") (class "Default")
      (node (ref "R3") (pin "2") (pinfunction "2_2") (pintype "passive"))
      (node (ref "R34") (pin "2") (pinfunction "2_2") (pintype "passive"))
      (node (ref "R35") (pin "1") (pinfunction "1_1") (pintype "passive"))
      (node (ref "R67") (pin "1") (pinfunction "1_1") (pintype "passive"))
    )
    (net (code "46") (name "Net-(R10-Pad2)") (class "Default")
      (node (ref "R10") (pin "2") (pinfunction "2_2") (pintype "passive"))
      (node (ref "R41") (pin "2") (pinfunction "2_2") (pintype "passive"))
      (node (ref "R42") (pin "1") (pinfunction "1_1") (pintype "passive"))
      (node (ref "R74") (pin "1") (pinfunction "1_1") (pintype "passive"))
    )
    (net (code "47") (name "Net-(R11-Pad2)") (class "Default")
      (node (ref "R11") (pin "2") (pinfunction "2_2") (pintype "passive"))
      (node (ref "R42") (pin "2") (pinfunction "2_2") (pintype "passive"))
      (node (ref "R43") (pin "1") (pinfunction "1_1") (pintype "passive"))
      (node (ref "R75") (pin "1") (pinfunction "1_1") (pintype "passive"))
    )
    (net (code "48") (name "Net-(R12-Pad2)") (class "Default")
      (node (ref "R12") (pin "2") (pinfunction "2_2") (pintype "passive"))
      (node (ref "R43") (pin "2") (pinfunction "2_2") (pintype "passive"))
      (node (ref "R44") (pin "1") (pinfunction "1_1") (pintype "passive"))
      (node (ref "R76") (pin "1") (pinfunction "1_1") (pintype "passive"))
    )
    (net (code "49") (name "Net-(R13-Pad2)") (class "Default")
      (node (ref "R13") (pin "2") (pinfunction "2_2") (pintype "passive"))
      (node (ref "R44") (pin "2") (pinfunction "2_2") (pintype "passive"))
      (node (ref "R45") (pin "1") (pinfunction "1_1") (pintype "passive"))
      (node (ref "R77") (pin "1") (pinfunction "1_1") (pintype "passive"))
    )
    (net (code "50") (name "Net-(R14-Pad2)") (class "Default")
      (node (ref "R14") (pin "2") (pinfunction "2_2") (pintype "passive"))
      (node (ref "R45") (pin "2") (pinfunction "2_2") (pintype "passive"))
      (node (ref "R46") (pin "1") (pinfunction "1_1") (pintype "passive"))
      (node (ref "R78") (pin "1") (pinfunction "1_1") (pintype "passive"))
    )
    (net (code "51") (name "Net-(R15-Pad2)") (class "Default")
      (node (ref "R15") (pin "2") (pinfunction "2_2") (pintype "passive"))
      (node (ref "R46") (pin "2") (pinfunction "2_2") (pintype "passive"))
      (node (ref "R47") (pin "1") (pinfunction "1_1") (pintype "passive"))
      (node (ref "R79") (pin "1") (pinfunction "1_1") (pintype "passive"))
    )
    (net (code "52") (name "Net-(R16-Pad2)") (class "Default")
      (node (ref "R16") (pin "2") (pinfunction "2_2") (pintype "passive"))
      (node (ref "R47") (pin "2") (pinfunction "2_2") (pintype "passive"))
      (node (ref "R48") (pin "1") (pinfunction "1_1") (pintype "passive"))
      (node (ref "R80") (pin "1") (pinfunction "1_1") (pintype "passive"))
    )
    (net (code "53") (name "Net-(R17-Pad2)") (class "Default")
      (node (ref "R17") (pin "2") (pinfunction "2_2") (pintype "passive"))
      (node (ref "R48") (pin "2") (pinfunction "2_2") (pintype "passive"))
      (node (ref "R49") (pin "1") (pinfunction "1_1") (pintype "passive"))
      (node (ref "R81") (pin "1") (pinfunction "1_1") (pintype "passive"))
    )
    (net (code "54") (name "Net-(R18-Pad2)") (class "Default")
      (node (ref "R18") (pin "2") (pinfunction "2_2") (pintype "passive"))
      (node (ref "R49") (pin "2") (pinfunction "2_2") (pintype "passive"))
      (node (ref "R50") (pin "1") (pinfunction "1_1") (pintype "passive"))
      (node (ref "R82") (pin "1") (pinfunction "1_1") (pintype "passive"))
    )
    (net (code "55") (name "Net-(R19-Pad2)") (class "Default")
      (node (ref "R19") (pin "2") (pinfunction "2_2") (pintype "passive"))
      (node (ref "R50") (pin "2") (pinfunction "2_2") (pintype "passive"))
      (node (ref "R51") (pin "1") (pinfunction "1_1") (pintype "passive"))
      (node (ref "R83") (pin "1") (pinfunction "1_1") (pintype "passive"))
    )
    (net (code "56") (name "Net-(R20-Pad2)") (class "Default")
      (node (ref "R20") (pin "2") (pinfunction "2_2") (pintype "passive"))
      (node (ref "R51") (pin "2") (pinfunction "2_2") (pintype "passive"))
      (node (ref "R52") (pin "1") (pinfunction "1_1") (pintype "passive"))
      (node (ref "R84") (pin "1") (pinfunction "1_1") (pintype "passive"))
    )
    (net (code "57") (name "Net-(R21-Pad2)") (class "Default")
      (node (ref "R21") (pin "2") (pinfunction "2_2") (pintype "passive"))
      (node (ref "R52") (pin "2") (pinfunction "2_2") (pintype "passive"))
      (node (ref "R53") (pin "1") (pinfunction "1_1") (pintype "passive"))
      (node (ref "R85") (pin "1") (pinfunction "1_1") (pintype "passive"))
    )
    (net (code "58") (name "Net-(R22-Pad2)") (class "Default")
      (node (ref "R22") (pin "2") (pinfunction "2_2") (pintype "passive"))
      (node (ref "R53") (pin "2") (pinfunction "2_2") (pintype "passive"))
      (node (ref "R54") (pin "1") (pinfunction "1_1") (pintype "passive"))
      (node (ref "R86") (pin "1") (pinfunction "1_1") (pintype "passive"))
    )
    (net (code "59") (name "Net-(R23-Pad2)") (class "Default")
      (node (ref "R23") (pin "2") (pinfunction "2_2") (pintype "passive"))
      (node (ref "R54") (pin "2") (pinfunction "2_2") (pintype "passive"))
      (node (ref "R55") (pin "1") (pinfunction "1_1") (pintype "passive"))
      (node (ref "R87") (pin "1") (pinfunction "1_1") (pintype "passive"))
    )
    (net (code "60") (name "Net-(R24-Pad2)") (class "Default")
      (node (ref "R24") (pin "2") (pinfunction "2_2") (pintype "passive"))
      (node (ref "R55") (pin "2") (pinfunction "2_2") (pintype "passive"))
      (node (ref "R56") (pin "1") (pinfunction "1_1") (pintype "passive"))
      (node (ref "R88") (pin "1") (pinfunction "1_1") (pintype "passive"))
    )
    (net (code "61") (name "Net-(R25-Pad2)") (class "Default")
      (node (ref "R25") (pin "2") (pinfunction "2_2") (pintype "passive"))
      (node (ref "R56") (pin "2") (pinfunction "2_2") (pintype "passive"))
      (node (ref "R57") (pin "1") (pinfunction "1_1") (pintype "passive"))
      (node (ref "R89") (pin "1") (pinfunction "1_1") (pintype "passive"))
    )
    (net (code "62") (name "Net-(R26-Pad2)") (class "Default")
      (node (ref "R26") (pin "2") (pinfunction "2_2") (pintype "passive"))
      (node (ref "R57") (pin "2") (pinfunction "2_2") (pintype "passive"))
      (node (ref "R58") (pin "1") (pinfunction "1_1") (pintype "passive"))
      (node (ref "R90") (pin "1") (pinfunction "1_1") (pintype "passive"))
    )
    (net (code "63") (name "Net-(R27-Pad2)") (class "Default")
      (node (ref "R27") (pin "2") (pinfunction "2_2") (pintype "passive"))
      (node (ref "R58") (pin "2") (pinfunction "2_2") (pintype "passive"))
      (node (ref "R59") (pin "1") (pinfunction "1_1") (pintype "passive"))
      (node (ref "R91") (pin "1") (pinfunction "1_1") (pintype "passive"))
    )
    (net (code "64") (name "Net-(R28-Pad2)") (class "Default")
      (node (ref "R28") (pin "2") (pinfunction "2_2") (pintype "passive"))
      (node (ref "R59") (pin "2") (pinfunction "2_2") (pintype "passive"))
      (node (ref "R60") (pin "1") (pinfunction "1_1") (pintype "passive"))
      (node (ref "R92") (pin "1") (pinfunction "1_1") (pintype "passive"))
    )
    (net (code "65") (name "Net-(R29-Pad2)") (class "Default")
      (node (ref "R29") (pin "2") (pinfunction "2_2") (pintype "passive"))
      (node (ref "R60") (pin "2") (pinfunction "2_2") (pintype "passive"))
      (node (ref "R61") (pin "1") (pinfunction "1_1") (pintype "passive"))
      (node (ref "R93") (pin "1") (pinfunction "1_1") (pintype "passive"))
    )
    (net (code "66") (name "Net-(R30-Pad2)") (class "Default")
      (node (ref "R30") (pin "2") (pinfunction "2_2") (pintype "passive"))
      (node (ref "R61") (pin "2") (pinfunction "2_2") (pintype "passive"))
      (node (ref "R62") (pin "1") (pinfunction "1_1") (pintype "passive"))
      (node (ref "R94") (pin "1") (pinfunction "1_1") (pintype "passive"))
    )
    (net (code "67") (name "Net-(R31-Pad2)") (class "Default")
      (node (ref "R31") (pin "2") (pinfunction "2_2") (pintype "passive"))
      (node (ref "R62") (pin "2") (pinfunction "2_2") (pintype "passive"))
      (node (ref "R63") (pin "1") (pinfunction "1_1") (pintype "passive"))
      (node (ref "R95") (pin "1") (pinfunction "1_1") (pintype "passive"))
    )
    (net (code "68") (name "Net-(R32-Pad2)") (class "Default")
      (node (ref "R32") (pin "2") (pinfunction "2_2") (pintype "passive"))
      (node (ref "R63") (pin "2") (pinfunction "2_2") (pintype "passive"))
      (node (ref "R64") (pin "1") (pinfunction "1_1") (pintype "passive"))
      (node (ref "R96") (pin "1") (pinfunction "1_1") (pintype "passive"))
    )
    (net (code "69") (name "Net-(R35-Pad2)") (class "Default")
      (node (ref "R35") (pin "2") (pinfunction "2_2") (pintype "passive"))
      (node (ref "R36") (pin "1") (pinfunction "1_1") (pintype "passive"))
      (node (ref "R4") (pin "2") (pinfunction "2_2") (pintype "passive"))
      (node (ref "R68") (pin "1") (pinfunction "1_1") (pintype "passive"))
    )
    (net (code "70") (name "Net-(R36-Pad2)") (class "Default")
      (node (ref "R36") (pin "2") (pinfunction "2_2") (pintype "passive"))
      (node (ref "R37") (pin "1") (pinfunction "1_1") (pintype "passive"))
      (node (ref "R5") (pin "2") (pinfunction "2_2") (pintype "passive"))
      (node (ref "R69") (pin "1") (pinfunction "1_1") (pintype "passive"))
    )
    (net (code "71") (name "Net-(R37-Pad2)") (class "Default")
      (node (ref "R37") (pin "2") (pinfunction "2_2") (pintype "passive"))
      (node (ref "R38") (pin "1") (pinfunction "1_1") (pintype "passive"))
      (node (ref "R6") (pin "2") (pinfunction "2_2") (pintype "passive"))
      (node (ref "R70") (pin "1") (pinfunction "1_1") (pintype "passive"))
    )
    (net (code "72") (name "Net-(R38-Pad2)") (class "Default")
      (node (ref "R38") (pin "2") (pinfunction "2_2") (pintype "passive"))
      (node (ref "R39") (pin "1") (pinfunction "1_1") (pintype "passive"))
      (node (ref "R7") (pin "2") (pinfunction "2_2") (pintype "passive"))
      (node (ref "R71") (pin "1") (pinfunction "1_1") (pintype "passive"))
    )
    (net (code "73") (name "Net-(R39-Pad2)") (class "Default")
      (node (ref "R39") (pin "2") (pinfunction "2_2") (pintype "passive"))
      (node (ref "R40") (pin "1") (pinfunction "1_1") (pintype "passive"))
      (node (ref "R72") (pin "1") (pinfunction "1_1") (pintype "passive"))
      (node (ref "R8") (pin "2") (pinfunction "2_2") (pintype "passive"))
    )
    (net (code "74") (name "Net-(R40-Pad2)") (class "Default")
      (node (ref "R40") (pin "2") (pinfunction "2_2") (pintype "passive"))
      (node (ref "R41") (pin "1") (pinfunction "1_1") (pintype "passive"))
      (node (ref "R73") (pin "1") (pinfunction "1_1") (pintype "passive"))
      (node (ref "R9") (pin "2") (pinfunction "2_2") (pintype "passive"))
    )
    (net (code "75") (name "Net-(R100-Pad1)") (class "Default")
      (node (ref "R100") (pin "1") (pinfunction "1_1") (pintype "passive"))
      (node (ref "R132") (pin "1") (pinfunction "1_1") (pintype "passive"))
      (node (ref "R68") (pin "2") (pinfunction "2_2") (pintype "passive"))
      (node (ref "R99") (pin "2") (pinfunction "2_2") (pintype "passive"))
    )
    (net (code "76") (name "Net-(R100-Pad2)") (class "Default")
      (node (ref "R100") (pin "2") (pinfunction "2_2") (pintype "passive"))
      (node (ref "R101") (pin "1") (pinfunction "1_1") (pintype "passive"))
      (node (ref "R133") (pin "1") (pinfunction "1_1") (pintype "passive"))
      (node (ref "R69") (pin "2") (pinfunction "2_2") (pintype "passive"))
    )
    (net (code "77") (name "Net-(R101-Pad2)") (class "Default")
      (node (ref "R101") (pin "2") (pinfunction "2_2") (pintype "passive"))
      (node (ref "R102") (pin "1") (pinfunction "1_1") (pintype "passive"))
      (node (ref "R134") (pin "1") (pinfunction "1_1") (pintype "passive"))
      (node (ref "R70") (pin "2") (pinfunction "2_2") (pintype "passive"))
    )
    (net (code "78") (name "Net-(R102-Pad2)") (class "Default")
      (node (ref "R102") (pin "2") (pinfunction "2_2") (pintype "passive"))
      (node (ref "R103") (pin "1") (pinfunction "1_1") (pintype "passive"))
      (node (ref "R135") (pin "1") (pinfunction "1_1") (pintype "passive"))
      (node (ref "R71") (pin "2") (pinfunction "2_2") (pintype "passive"))
    )
    (net (code "79") (name "Net-(R103-Pad2)") (class "Default")
      (node (ref "R103") (pin "2") (pinfunction "2_2") (pintype "passive"))
      (node (ref "R104") (pin "1") (pinfunction "1_1") (pintype "passive"))
      (node (ref "R136") (pin "1") (pinfunction "1_1") (pintype "passive"))
      (node (ref "R72") (pin "2") (pinfunction "2_2") (pintype "passive"))
    )
    (net (code "80") (name "Net-(R104-Pad2)") (class "Default")
      (node (ref "R104") (pin "2") (pinfunction "2_2") (pintype "passive"))
      (node (ref "R105") (pin "1") (pinfunction "1_1") (pintype "passive"))
      (node (ref "R137") (pin "1") (pinfunction "1_1") (pintype "passive"))
      (node (ref "R73") (pin "2") (pinfunction "2_2") (pintype "passive"))
    )
    (net (code "81") (name "Net-(R106-Pad2)") (class "Default")
      (node (ref "R106") (pin "2") (pinfunction "2_2") (pintype "passive"))
      (node (ref "R107") (pin "1") (pinfunction "1_1") (pintype "passive"))
      (node (ref "R139") (pin "1") (pinfunction "1_1") (pintype "passive"))
      (node (ref "R75") (pin "2") (pinfunction "2_2") (pintype "passive"))
    )
    (net (code "82") (name "Net-(R107-Pad2)") (class "Default")
      (node (ref "R107") (pin "2") (pinfunction "2_2") (pintype "passive"))
      (node (ref "R108") (pin "1") (pinfunction "1_1") (pintype "passive"))
      (node (ref "R140") (pin "1") (pinfunction "1_1") (pintype "passive"))
      (node (ref "R76") (pin "2") (pinfunction "2_2") (pintype "passive"))
    )
    (net (code "83") (name "Net-(R108-Pad2)") (class "Default")
      (node (ref "R108") (pin "2") (pinfunction "2_2") (pintype "passive"))
      (node (ref "R109") (pin "1") (pinfunction "1_1") (pintype "passive"))
      (node (ref "R141") (pin "1") (pinfunction "1_1") (pintype "passive"))
      (node (ref "R77") (pin "2") (pinfunction "2_2") (pintype "passive"))
    )
    (net (code "84") (name "Net-(R109-Pad2)") (class "Default")
      (node (ref "R109") (pin "2") (pinfunction "2_2") (pintype "passive"))
      (node (ref "R110") (pin "1") (pinfunction "1_1") (pintype "passive"))
      (node (ref "R142") (pin "1") (pinfunction "1_1") (pintype "passive"))
      (node (ref "R78") (pin "2") (pinfunction "2_2") (pintype "passive"))
    )
    (net (code "85") (name "Net-(R110-Pad2)") (class "Default")
      (node (ref "R110") (pin "2") (pinfunction "2_2") (pintype "passive"))
      (node (ref "R111") (pin "1") (pinfunction "1_1") (pintype "passive"))
      (node (ref "R143") (pin "1") (pinfunction "1_1") (pintype "passive"))
      (node (ref "R79") (pin "2") (pinfunction "2_2") (pintype "passive"))
    )
    (net (code "86") (name "Net-(R111-Pad2)") (class "Default")
      (node (ref "R111") (pin "2") (pinfunction "2_2") (pintype "passive"))
      (node (ref "R112") (pin "1") (pinfunction "1_1") (pintype "passive"))
      (node (ref "R144") (pin "1") (pinfunction "1_1") (pintype "passive"))
      (node (ref "R80") (pin "2") (pinfunction "2_2") (pintype "passive"))
    )
    (net (code "87") (name "Net-(R112-Pad2)") (class "Default")
      (node (ref "R112") (pin "2") (pinfunction "2_2") (pintype "passive"))
      (node (ref "R113") (pin "1") (pinfunction "1_1") (pintype "passive"))
      (node (ref "R145") (pin "1") (pinfunction "1_1") (pintype "passive"))
      (node (ref "R81") (pin "2") (pinfunction "2_2") (pintype "passive"))
    )
    (net (code "88") (name "Net-(R113-Pad2)") (class "Default")
      (node (ref "R113") (pin "2") (pinfunction "2_2") (pintype "passive"))
      (node (ref "R114") (pin "1") (pinfunction "1_1") (pintype "passive"))
      (node (ref "R146") (pin "1") (pinfunction "1_1") (pintype "passive"))
      (node (ref "R82") (pin "2") (pinfunction "2_2") (pintype "passive"))
    )
    (net (code "89") (name "Net-(R114-Pad2)") (class "Default")
      (node (ref "R114") (pin "2") (pinfunction "2_2") (pintype "passive"))
      (node (ref "R115") (pin "1") (pinfunction "1_1") (pintype "passive"))
      (node (ref "R147") (pin "1") (pinfunction "1_1") (pintype "passive"))
      (node (ref "R83") (pin "2") (pinfunction "2_2") (pintype "passive"))
    )
    (net (code "90") (name "Net-(R116-Pad2)") (class "Default")
      (node (ref "R116") (pin "2") (pinfunction "2_2") (pintype "passive"))
      (node (ref "R117") (pin "1") (pinfunction "1_1") (pintype "passive"))
      (node (ref "R149") (pin "1") (pinfunction "1_1") (pintype "passive"))
      (node (ref "R85") (pin "2") (pinfunction "2_2") (pintype "passive"))
    )
    (net (code "91") (name "Net-(R117-Pad2)") (class "Default")
      (node (ref "R117") (pin "2") (pinfunction "2_2") (pintype "passive"))
      (node (ref "R118") (pin "1") (pinfunction "1_1") (pintype "passive"))
      (node (ref "R150") (pin "1") (pinfunction "1_1") (pintype "passive"))
      (node (ref "R86") (pin "2") (pinfunction "2_2") (pintype "passive"))
    )
    (net (code "92") (name "Net-(R118-Pad2)") (class "Default")
      (node (ref "R118") (pin "2") (pinfunction "2_2") (pintype "passive"))
      (node (ref "R119") (pin "1") (pinfunction "1_1") (pintype "passive"))
      (node (ref "R151") (pin "1") (pinfunction "1_1") (pintype "passive"))
      (node (ref "R87") (pin "2") (pinfunction "2_2") (pintype "passive"))
    )
    (net (code "93") (name "Net-(R119-Pad2)") (class "Default")
      (node (ref "R119") (pin "2") (pinfunction "2_2") (pintype "passive"))
      (node (ref "R120") (pin "1") (pinfunction "1_1") (pintype "passive"))
      (node (ref "R152") (pin "1") (pinfunction "1_1") (pintype "passive"))
      (node (ref "R88") (pin "2") (pinfunction "2_2") (pintype "passive"))
    )
    (net (code "94") (name "Net-(R120-Pad2)") (class "Default")
      (node (ref "R120") (pin "2") (pinfunction "2_2") (pintype "passive"))
      (node (ref "R121") (pin "1") (pinfunction "1_1") (pintype "passive"))
      (node (ref "R153") (pin "1") (pinfunction "1_1") (pintype "passive"))
      (node (ref "R89") (pin "2") (pinfunction "2_2") (pintype "passive"))
    )
    (net (code "95") (name "Net-(R121-Pad2)") (class "Default")
      (node (ref "R121") (pin "2") (pinfunction "2_2") (pintype "passive"))
      (node (ref "R122") (pin "1") (pinfunction "1_1") (pintype "passive"))
      (node (ref "R154") (pin "1") (pinfunction "1_1") (pintype "passive"))
      (node (ref "R90") (pin "2") (pinfunction "2_2") (pintype "passive"))
    )
    (net (code "96") (name "Net-(R122-Pad2)") (class "Default")
      (node (ref "R122") (pin "2") (pinfunction "2_2") (pintype "passive"))
      (node (ref "R123") (pin "1") (pinfunction "1_1") (pintype "passive"))
      (node (ref "R155") (pin "1") (pinfunction "1_1") (pintype "passive"))
      (node (ref "R91") (pin "2") (pinfunction "2_2") (pintype "passive"))
    )
    (net (code "97") (name "Net-(R123-Pad2)") (class "Default")
      (node (ref "R123") (pin "2") (pinfunction "2_2") (pintype "passive"))
      (node (ref "R124") (pin "1") (pinfunction "1_1") (pintype "passive"))
      (node (ref "R156") (pin "1") (pinfunction "1_1") (pintype "passive"))
      (node (ref "R92") (pin "2") (pinfunction "2_2") (pintype "passive"))
    )
    (net (code "98") (name "Net-(R124-Pad2)") (class "Default")
      (node (ref "R124") (pin "2") (pinfunction "2_2") (pintype "passive"))
      (node (ref "R125") (pin "1") (pinfunction "1_1") (pintype "passive"))
      (node (ref "R157") (pin "1") (pinfunction "1_1") (pintype "passive"))
      (node (ref "R93") (pin "2") (pinfunction "2_2") (pintype "passive"))
    )
    (net (code "99") (name "Net-(R126-Pad2)") (class "Default")
      (node (ref "R126") (pin "2") (pinfunction "2_2") (pintype "passive"))
      (node (ref "R127") (pin "1") (pinfunction "1_1") (pintype "passive"))
      (node (ref "R159") (pin "1") (pinfunction "1_1") (pintype "passive"))
      (node (ref "R95") (pin "2") (pinfunction "2_2") (pintype "passive"))
    )
    (net (code "100") (name "Net-(R127-Pad2)") (class "Default")
      (node (ref "R127") (pin "2") (pinfunction "2_2") (pintype "passive"))
      (node (ref "R128") (pin "1") (pinfunction "1_1") (pintype "passive"))
      (node (ref "R160") (pin "1") (pinfunction "1_1") (pintype "passive"))
      (node (ref "R96") (pin "2") (pinfunction "2_2") (pintype "passive"))
    )
    (net (code "101") (name "Net-(R128-Pad2)") (class "Default")
      (node (ref "R128") (pin "2") (pinfunction "2_2") (pintype "passive"))
      (node (ref "R129") (pin "1") (pinfunction "1_1") (pintype "passive"))
      (node (ref "R65") (pin "2") (pinfunction "2_2") (pintype "passive"))
      (node (ref "R97") (pin "1") (pinfunction "1_1") (pintype "passive"))
    )
    (net (code "102") (name "Net-(R130-Pad1)") (class "Default")
      (node (ref "R130") (pin "1") (pinfunction "1_1") (pintype "passive"))
      (node (ref "R66") (pin "2") (pinfunction "2_2") (pintype "passive"))
      (node (ref "R97") (pin "2") (pinfunction "2_2") (pintype "passive"))
      (node (ref "R98") (pin "1") (pinfunction "1_1") (pintype "passive"))
    )
    (net (code "103") (name "Net-(R131-Pad1)") (class "Default")
      (node (ref "R131") (pin "1") (pinfunction "1_1") (pintype "passive"))
      (node (ref "R67") (pin "2") (pinfunction "2_2") (pintype "passive"))
      (node (ref "R98") (pin "2") (pinfunction "2_2") (pintype "passive"))
      (node (ref "R99") (pin "1") (pinfunction "1_1") (pintype "passive"))
    )
    (net (code "104") (name "Net-(R163-Pad2)") (class "Default")
      (node (ref "R163") (pin "2") (pinfunction "2_2") (pintype "passive"))
      (node (ref "R164") (pin "2") (pinfunction "2_2") (pintype "passive"))
    )
    (net (code "105") (name "Net-(R164-Pad1)") (class "Default")
      (node (ref "R164") (pin "1") (pinfunction "1_1") (pintype "passive"))
      (node (ref "R165") (pin "1") (pinfunction "1_1") (pintype "passive"))
    )
    (net (code "106") (name "Net-(R165-Pad2)") (class "Default")
      (node (ref "R165") (pin "2") (pinfunction "2_2") (pintype "passive"))
      (node (ref "R168") (pin "2") (pinfunction "2_2") (pintype "passive"))
    )
    (net (code "107") (name "Net-(R168-Pad1)") (class "Default")
      (node (ref "R168") (pin "1") (pinfunction "1_1") (pintype "passive"))
      (node (ref "R171") (pin "1") (pinfunction "1_1") (pintype "passive"))
    )
    (net (code "108") (name "Net-(R172-Pad2)") (class "Default")
      (node (ref "R172") (pin "2") (pinfunction "2_2") (pintype "passive"))
      (node (ref "R173") (pin "2") (pinfunction "2_2") (pintype "passive"))
    )
    (net (code "109") (name "Net-(R173-Pad1)") (class "Default")
      (node (ref "R173") (pin "1") (pinfunction "1_1") (pintype "passive"))
      (node (ref "R174") (pin "1") (pinfunction "1_1") (pintype "passive"))
    )
    (net (code "110") (name "Net-(R174-Pad2)") (class "Default")
      (node (ref "R174") (pin "2") (pinfunction "2_2") (pintype "passive"))
      (node (ref "R175") (pin "2") (pinfunction "2_2") (pintype "passive"))
    )
    (net (code "111") (name "Net-(R176-Pad2)") (class "Default")
      (node (ref "R176") (pin "2") (pinfunction "2_2") (pintype "passive"))
      (node (ref "R177") (pin "1") (pinfunction "1_1") (pintype "passive"))
    )
    (net (code "112") (name "Net-(R177-Pad2)") (class "Default")
      (node (ref "R177") (pin "2") (pinfunction "2_2") (pintype "passive"))
      (node (ref "R178") (pin "1") (pinfunction "1_1") (pintype "passive"))
    )
    (net (code "113") (name "SW_IN1") (class "Default")
      (node (ref "K1") (pin "4") (pinfunction "DS1_4") (pintype "passive"))
      (node (ref "R105") (pin "2") (pinfunction "2_2") (pintype "passive"))
      (node (ref "R106") (pin "1") (pinfunction "1_1") (pintype "passive"))
      (node (ref "R138") (pin "1") (pinfunction "1_1") (pintype "passive"))
      (node (ref "R74") (pin "2") (pinfunction "2_2") (pintype "passive"))
    )
    (net (code "114") (name "SW_IN2") (class "Default")
      (node (ref "K2") (pin "4") (pinfunction "DS1_4") (pintype "passive"))
      (node (ref "R115") (pin "2") (pinfunction "2_2") (pintype "passive"))
      (node (ref "R116") (pin "1") (pinfunction "1_1") (pintype "passive"))
      (node (ref "R148") (pin "1") (pinfunction "1_1") (pintype "passive"))
      (node (ref "R84") (pin "2") (pinfunction "2_2") (pintype "passive"))
    )
    (net (code "115") (name "SW_IN3") (class "Default")
      (node (ref "K3") (pin "4") (pinfunction "DS1_4") (pintype "passive"))
      (node (ref "R125") (pin "2") (pinfunction "2_2") (pintype "passive"))
      (node (ref "R126") (pin "1") (pinfunction "1_1") (pintype "passive"))
      (node (ref "R158") (pin "1") (pinfunction "1_1") (pintype "passive"))
      (node (ref "R94") (pin "2") (pinfunction "2_2") (pintype "passive"))
    )
    (net (code "116") (name "SW_OUT1") (class "Default")
      (node (ref "K1") (pin "3") (pinfunction "DS2_3") (pintype "passive"))
      (node (ref "R163") (pin "1") (pinfunction "1_1") (pintype "passive"))
    )
    (net (code "117") (name "SW_OUT2") (class "Default")
      (node (ref "K2") (pin "3") (pinfunction "DS2_3") (pintype "passive"))
      (node (ref "R172") (pin "1") (pinfunction "1_1") (pintype "passive"))
    )
    (net (code "118") (name "SW_OUT3") (class "Default")
      (node (ref "K3") (pin "3") (pinfunction "DS2_3") (pintype "passive"))
      (node (ref "R176") (pin "1") (pinfunction "1_1") (pintype "passive"))
    )
  )
)
